# TDA2822M.net
KiCad netlist of a schematic drawn in EAGLE
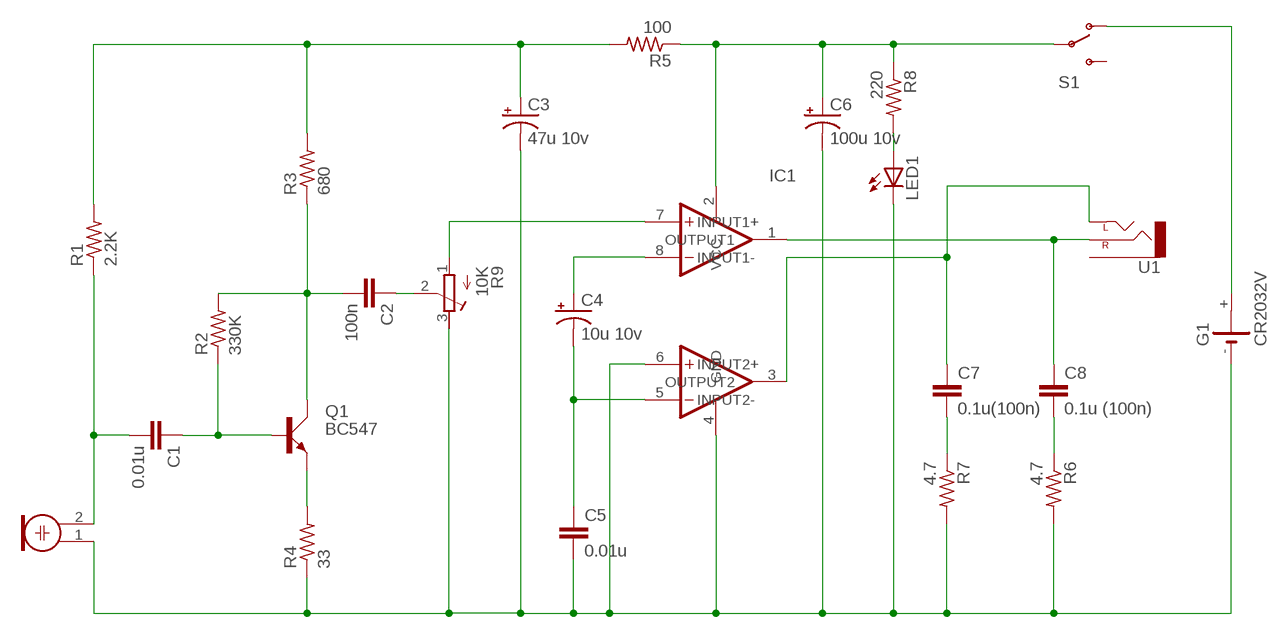
[diagram p0: schematic, sheet 1]

(export (version "E")
  (design (tool "Eeschema 10.0.6"))
  (components
    (comp (ref "C1")
      (value "0.01u")
      (footprint "eagle-import:CAP-PTH-SMALL")
      (libsource (lib "eagle-import") (part "CAPPTH"))
    )
    (comp (ref "C2")
      (value "100n")
      (footprint "eagle-import:CAP-PTH-SMALL")
      (libsource (lib "eagle-import") (part "CAPPTH"))
    )
    (comp (ref "C3")
      (value "47u 10v")
      (footprint "eagle-import:CPOL-RADIAL-10UF-25V")
      (libsource (lib "eagle-import") (part "CAP_POLPTH2"))
    )
    (comp (ref "C4")
      (value "10u 10v")
      (footprint "eagle-import:CPOL-RADIAL-10UF-25V")
      (libsource (lib "eagle-import") (part "CAP_POLPTH2"))
    )
    (comp (ref "C5")
      (value "0.01u")
      (footprint "eagle-import:CAP-PTH-SMALL")
      (libsource (lib "eagle-import") (part "CAPPTH"))
    )
    (comp (ref "C6")
      (value "100u 10v")
      (footprint "eagle-import:CPOL-RADIAL-10UF-25V")
      (libsource (lib "eagle-import") (part "CAP_POLPTH2"))
    )
    (comp (ref "C7")
      (value "0.1u(100n)")
      (footprint "eagle-import:CAP-PTH-SMALL")
      (libsource (lib "eagle-import") (part "CAPPTH"))
    )
    (comp (ref "C8")
      (value "0.1u (100n)")
      (footprint "eagle-import:CAP-PTH-SMALL")
      (libsource (lib "eagle-import") (part "CAPPTH"))
    )
    (comp (ref "G1")
      (value "CR2032V")
      (footprint "eagle-import:CR2032V")
      (libsource (lib "eagle-import") (part "CR2032V"))
    )
    (comp (ref "IC1")
      (value "TDA2822M")
      (footprint "eagle-import:DIL8")
      (libsource (lib "eagle-import") (part "TDA2822M"))
    )
    (comp (ref "LED1")
      (value "LED3MM")
      (footprint "eagle-import:LED3MM")
      (libsource (lib "eagle-import") (part "LED3MM"))
    )
    (comp (ref "M1")
      (value "ELECTRET_MICROPHON-F6035AP")
      (footprint "eagle-import:F6035AP")
      (libsource (lib "eagle-import") (part "ELECTRET_MICROPHON-F6035AP"))
    )
    (comp (ref "Q1")
      (value "BC547")
      (footprint "eagle-import:SOT54A")
      (libsource (lib "eagle-import") (part "BC547"))
    )
    (comp (ref "R1")
      (value "2.2K")
      (footprint "eagle-import:0204_7")
      (libsource (lib "eagle-import") (part "R-US_0204/7"))
    )
    (comp (ref "R2")
      (value "330K")
      (footprint "eagle-import:0204_7")
      (libsource (lib "eagle-import") (part "R-US_0204/7"))
    )
    (comp (ref "R3")
      (value "680")
      (footprint "eagle-import:0204_7")
      (libsource (lib "eagle-import") (part "R-US_0204/7"))
    )
    (comp (ref "R4")
      (value "33")
      (footprint "eagle-import:0204_7")
      (libsource (lib "eagle-import") (part "R-US_0204/7"))
    )
    (comp (ref "R5")
      (value "100")
      (footprint "eagle-import:0204_7")
      (libsource (lib "eagle-import") (part "R-US_0204/7"))
    )
    (comp (ref "R6")
      (value "4.7")
      (footprint "eagle-import:0204_7")
      (libsource (lib "eagle-import") (part "R-US_0204/7"))
    )
    (comp (ref "R7")
      (value "4.7")
      (footprint "eagle-import:0204_7")
      (libsource (lib "eagle-import") (part "R-US_0204/7"))
    )
    (comp (ref "R8")
      (value "220")
      (footprint "eagle-import:0204_7")
      (libsource (lib "eagle-import") (part "R-US_0204/7"))
    )
    (comp (ref "R9")
      (value "10K")
      (footprint "eagle-import:RTRIM3339P")
      (libsource (lib "eagle-import") (part "R-TRIMM3339P"))
    )
    (comp (ref "S1")
      (value "SWITCH-SPSTKIT")
      (footprint "eagle-import:SWITCH-SPDT_KIT")
      (libsource (lib "eagle-import") (part "SWITCH-SPSTKIT"))
    )
    (comp (ref "U1")
      (value "AUDIO-JACKPTH")
      (footprint "eagle-import:AUDIO-JACK")
      (libsource (lib "eagle-import") (part "AUDIO-JACKPTH"))
    )
  )
  (nets
    (net (code "1") (name "Net-(C1-Pad1)") (class "Default")
      (node (ref "C1") (pin "1") (pinfunction "1_1") (pintype "passive"))
      (node (ref "Q1") (pin "B") (pinfunction "B_B") (pintype "passive"))
      (node (ref "R2") (pin "1") (pinfunction "1_1") (pintype "passive"))
    )
    (net (code "2") (name "Net-(C1-Pad2)") (class "Default")
      (node (ref "C1") (pin "2") (pinfunction "2_2") (pintype "passive"))
      (node (ref "M1") (pin "2") (pinfunction "2_2") (pintype "passive"))
      (node (ref "R1") (pin "1") (pinfunction "1_1") (pintype "passive"))
    )
    (net (code "3") (name "Net-(C2-Pad2)") (class "Default")
      (node (ref "C2") (pin "2") (pinfunction "2_2") (pintype "passive"))
      (node (ref "Q1") (pin "C") (pinfunction "C_C") (pintype "passive"))
      (node (ref "R2") (pin "2") (pinfunction "2_2") (pintype "passive"))
      (node (ref "R3") (pin "1") (pinfunction "1_1") (pintype "passive"))
    )
    (net (code "4") (name "Net-(C3-+)") (class "Default")
      (node (ref "C3") (pin "1") (pinfunction "+_1") (pintype "passive"))
      (node (ref "R1") (pin "2") (pinfunction "2_2") (pintype "passive"))
      (node (ref "R3") (pin "2") (pinfunction "2_2") (pintype "passive"))
      (node (ref "R5") (pin "2") (pinfunction "2_2") (pintype "passive"))
    )
    (net (code "5") (name "Net-(C3--)") (class "Default")
      (node (ref "C3") (pin "2") (pinfunction "-_2") (pintype "passive"))
      (node (ref "C5") (pin "2") (pinfunction "2_2") (pintype "passive"))
      (node (ref "C6") (pin "2") (pinfunction "-_2") (pintype "passive"))
      (node (ref "G1") (pin "-") (pinfunction "-_-") (pintype "passive"))
      (node (ref "IC1") (pin "4") (pinfunction "GND_4") (pintype "bidirectional"))
      (node (ref "IC1") (pin "6") (pinfunction "INPUT2+_6") (pintype "bidirectional"))
      (node (ref "LED1") (pin "K") (pinfunction "C_K") (pintype "passive"))
      (node (ref "M1") (pin "1") (pinfunction "1_1") (pintype "passive"))
      (node (ref "R4") (pin "1") (pinfunction "1_1") (pintype "passive"))
      (node (ref "R6") (pin "2") (pinfunction "2_2") (pintype "passive"))
      (node (ref "R7") (pin "2") (pinfunction "2_2") (pintype "passive"))
      (node (ref "R9") (pin "3") (pinfunction "A_3") (pintype "passive"))
    )
    (net (code "6") (name "Net-(C4-+)") (class "Default")
      (node (ref "C4") (pin "1") (pinfunction "+_1") (pintype "passive"))
      (node (ref "IC1") (pin "8") (pinfunction "INPUT1-_8") (pintype "bidirectional"))
    )
    (net (code "7") (name "Net-(C4--)") (class "Default")
      (node (ref "C4") (pin "2") (pinfunction "-_2") (pintype "passive"))
      (node (ref "C5") (pin "1") (pinfunction "1_1") (pintype "passive"))
      (node (ref "IC1") (pin "5") (pinfunction "INPUT2-_5") (pintype "bidirectional"))
    )
    (net (code "8") (name "Net-(C6-+)") (class "Default")
      (node (ref "C6") (pin "1") (pinfunction "+_1") (pintype "passive"))
      (node (ref "IC1") (pin "2") (pinfunction "VCC_2") (pintype "bidirectional"))
      (node (ref "R5") (pin "1") (pinfunction "1_1") (pintype "passive"))
      (node (ref "R8") (pin "1") (pinfunction "1_1") (pintype "passive"))
      (node (ref "S1") (pin "2") (pinfunction "P_2") (pintype "passive"))
    )
    (net (code "9") (name "Net-(C7-Pad2)") (class "Default")
      (node (ref "C7") (pin "2") (pinfunction "2_2") (pintype "passive"))
      (node (ref "R7") (pin "1") (pinfunction "1_1") (pintype "passive"))
    )
    (net (code "10") (name "Net-(C8-Pad2)") (class "Default")
      (node (ref "C8") (pin "2") (pinfunction "2_2") (pintype "passive"))
      (node (ref "R6") (pin "1") (pinfunction "1_1") (pintype "passive"))
    )
    (net (code "11") (name "Net-(IC1-INPUT1+)") (class "Default")
      (node (ref "IC1") (pin "7") (pinfunction "INPUT1+_7") (pintype "bidirectional"))
      (node (ref "R9") (pin "1") (pinfunction "E_1") (pintype "passive"))
    )
    (net (code "12") (name "Net-(IC1-OUTPUT1)") (class "Default")
      (node (ref "C8") (pin "1") (pinfunction "1_1") (pintype "passive"))
      (node (ref "IC1") (pin "1") (pinfunction "OUTPUT1_1") (pintype "bidirectional"))
      (node (ref "U1") (pin "RING") (pinfunction "RIGHT_RING") (pintype "bidirectional"))
    )
    (net (code "13") (name "Net-(IC1-OUTPUT2)") (class "Default")
      (node (ref "C7") (pin "1") (pinfunction "1_1") (pintype "passive"))
      (node (ref "IC1") (pin "3") (pinfunction "OUTPUT2_3") (pintype "bidirectional"))
      (node (ref "U1") (pin "TIP") (pinfunction "LEFT_TIP") (pintype "bidirectional"))
    )
    (net (code "14") (name "Net-(LED1-PadA)") (class "Default")
      (node (ref "LED1") (pin "A") (pinfunction "A_A") (pintype "passive"))
      (node (ref "R8") (pin "2") (pinfunction "2_2") (pintype "passive"))
    )
    (net (code "15") (name "Net-(Q1-PadE)") (class "Default")
      (node (ref "Q1") (pin "E") (pinfunction "E_E") (pintype "passive"))
      (node (ref "R4") (pin "2") (pinfunction "2_2") (pintype "passive"))
    )
    (net (code "16") (name "Net-(R9-S)") (class "Default")
      (node (ref "C2") (pin "1") (pinfunction "1_1") (pintype "passive"))
      (node (ref "R9") (pin "2") (pinfunction "S_2") (pintype "passive"))
    )
    (net (code "17") (name "Net-(S1-O)") (class "Default")
      (node (ref "G1") (pin "+") (pinfunction "+_+") (pintype "passive"))
      (node (ref "S1") (pin "1") (pinfunction "O_1") (pintype "passive"))
    )
    (net (code "18") (name "unconnected-(G1-+-Pad+@1)") (class "Default")
      (node (ref "G1") (pin "+@1") (pinfunction "+_+@1") (pintype "passive"))
    )
    (net (code "19") (name "unconnected-(S1-S-Pad3)") (class "Default")
      (node (ref "S1") (pin "3") (pinfunction "S_3") (pintype "passive"))
    )
    (net (code "20") (name "unconnected-(U1-PadSLEEVE)") (class "Default")
      (node (ref "U1") (pin "SLEEVE") (pinfunction "SLEEVE_SLEEVE") (pintype "bidirectional"))
    )
  )
)
